# Sheet1.net
KiCad netlist of a schematic drawn in Altium Designer
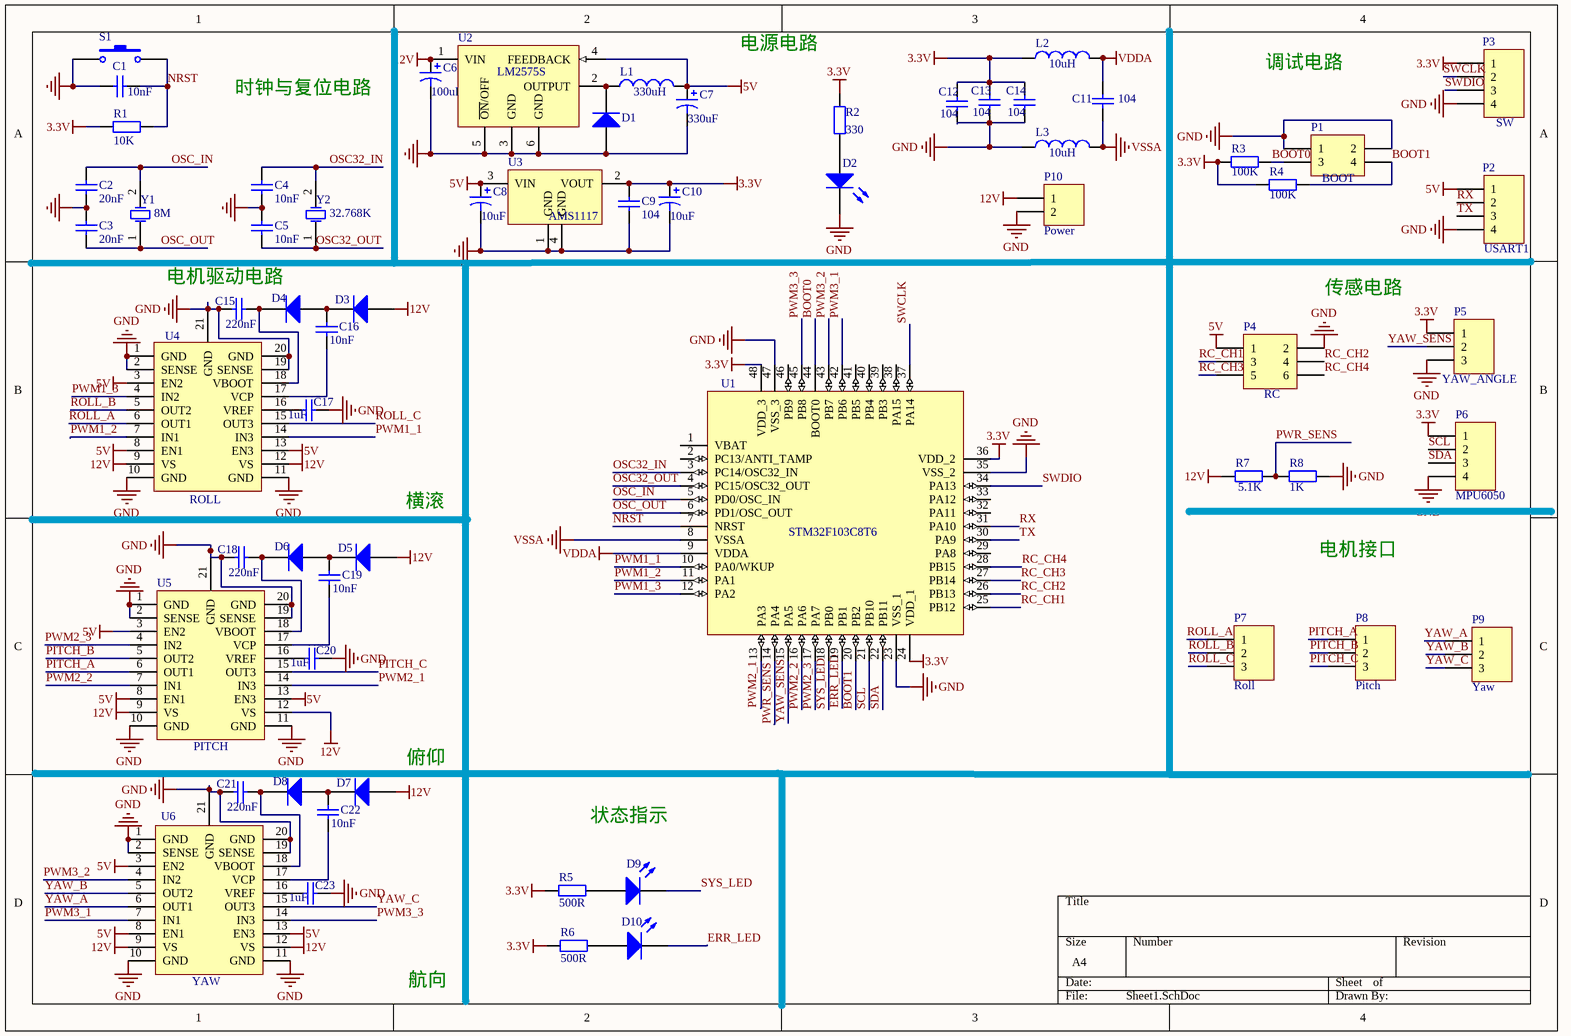
[diagram p0: Sheet1.SchDoc]

(export (version "E")
  (design (tool "Eeschema 10.0.6"))
  (components
    (comp (ref "C1")
      (value "10nF")
      (footprint "0603")
      (description "Capacitor")
      (fields (field (name "Comment") "Cap") (field (name "PUBLISHER") "Altium Limited"))
      (libsource (lib "Miscellaneous Devices") (part "Cap"))
    )
    (comp (ref "C2")
      (value "20nF")
      (footprint "0603")
      (description "Capacitor")
      (fields (field (name "Comment") "Cap") (field (name "PUBLISHER") "Altium Limited"))
      (libsource (lib "Miscellaneous Devices") (part "Cap"))
    )
    (comp (ref "C3")
      (value "20nF")
      (footprint "0603")
      (description "Capacitor")
      (fields (field (name "Comment") "Cap") (field (name "PUBLISHER") "Altium Limited"))
      (libsource (lib "Miscellaneous Devices") (part "Cap"))
    )
    (comp (ref "C4")
      (value "10nF")
      (footprint "0603")
      (description "Capacitor")
      (fields (field (name "Comment") "Cap") (field (name "PUBLISHER") "Altium Limited"))
      (libsource (lib "Miscellaneous Devices") (part "Cap"))
    )
    (comp (ref "C5")
      (value "10nF")
      (footprint "0603")
      (description "Capacitor")
      (fields (field (name "Comment") "Cap") (field (name "PUBLISHER") "Altium Limited"))
      (libsource (lib "Miscellaneous Devices") (part "Cap"))
    )
    (comp (ref "C6")
      (value "100uF")
      (footprint "25V 100uF 6*7")
      (description "Polarized Capacitor (Radial)")
      (fields (field (name "Comment") "Cap Pol1") (field (name "PUBLISHER") "Altium Limited"))
      (libsource (lib "Miscellaneous Devices") (part "Cap Pol1"))
    )
    (comp (ref "C7")
      (value "330uF")
      (footprint "25V 330uF 8*10")
      (description "Polarized Capacitor (Radial)")
      (fields (field (name "Comment") "Cap Pol1") (field (name "PUBLISHER") "Altium Limited"))
      (libsource (lib "Miscellaneous Devices") (part "Cap Pol1"))
    )
    (comp (ref "C8")
      (value "10uF")
      (footprint "1206")
      (description "Polarized Capacitor (Radial)")
      (fields (field (name "Comment") "Cap Pol1") (field (name "PUBLISHER") "Altium Limited"))
      (libsource (lib "Miscellaneous Devices") (part "Cap Pol1"))
    )
    (comp (ref "C9")
      (value "104")
      (footprint "0603")
      (description "Capacitor")
      (fields (field (name "Comment") "Cap") (field (name "PUBLISHER") "Altium Limited"))
      (libsource (lib "Miscellaneous Devices") (part "Cap"))
    )
    (comp (ref "C10")
      (value "10uF")
      (footprint "1206")
      (description "Polarized Capacitor (Radial)")
      (fields (field (name "Comment") "Cap Pol1") (field (name "PUBLISHER") "Altium Limited"))
      (libsource (lib "Miscellaneous Devices") (part "Cap Pol1"))
    )
    (comp (ref "C11")
      (value "104")
      (footprint "0603")
      (description "Capacitor")
      (fields (field (name "Comment") "Cap") (field (name "PUBLISHER") "Altium Limited"))
      (libsource (lib "Miscellaneous Devices") (part "Cap"))
    )
    (comp (ref "C12")
      (value "104")
      (footprint "0603")
      (description "Capacitor")
      (fields (field (name "Comment") "Cap") (field (name "PUBLISHER") "Altium Limited"))
      (libsource (lib "Miscellaneous Devices") (part "Cap"))
    )
    (comp (ref "C13")
      (value "104")
      (footprint "0603")
      (description "Capacitor")
      (fields (field (name "Comment") "Cap") (field (name "PUBLISHER") "Altium Limited"))
      (libsource (lib "Miscellaneous Devices") (part "Cap"))
    )
    (comp (ref "C14")
      (value "104")
      (footprint "0603")
      (description "Capacitor")
      (fields (field (name "Comment") "Cap") (field (name "PUBLISHER") "Altium Limited"))
      (libsource (lib "Miscellaneous Devices") (part "Cap"))
    )
    (comp (ref "C15")
      (value "220nF")
      (footprint "0603")
      (description "Capacitor")
      (fields (field (name "Comment") "Cap") (field (name "PUBLISHER") "Altium Limited"))
      (libsource (lib "Miscellaneous Devices") (part "Cap"))
    )
    (comp (ref "C16")
      (value "10nF")
      (footprint "0603")
      (description "Capacitor")
      (fields (field (name "Comment") "Cap") (field (name "PUBLISHER") "Altium Limited"))
      (libsource (lib "Miscellaneous Devices") (part "Cap"))
    )
    (comp (ref "C17")
      (value "1uF")
      (footprint "0603")
      (description "Capacitor")
      (fields (field (name "Comment") "Cap") (field (name "PUBLISHER") "Altium Limited"))
      (libsource (lib "Miscellaneous Devices") (part "Cap"))
    )
    (comp (ref "C18")
      (value "220nF")
      (footprint "0603")
      (description "Capacitor")
      (fields (field (name "Comment") "Cap") (field (name "PUBLISHER") "Altium Limited"))
      (libsource (lib "Miscellaneous Devices") (part "Cap"))
    )
    (comp (ref "C19")
      (value "10nF")
      (footprint "0603")
      (description "Capacitor")
      (fields (field (name "Comment") "Cap") (field (name "PUBLISHER") "Altium Limited"))
      (libsource (lib "Miscellaneous Devices") (part "Cap"))
    )
    (comp (ref "C20")
      (value "1uF")
      (footprint "0603")
      (description "Capacitor")
      (fields (field (name "Comment") "Cap") (field (name "PUBLISHER") "Altium Limited"))
      (libsource (lib "Miscellaneous Devices") (part "Cap"))
    )
    (comp (ref "C21")
      (value "220nF")
      (footprint "0603")
      (description "Capacitor")
      (fields (field (name "Comment") "Cap") (field (name "PUBLISHER") "Altium Limited"))
      (libsource (lib "Miscellaneous Devices") (part "Cap"))
    )
    (comp (ref "C22")
      (value "10nF")
      (footprint "0603")
      (description "Capacitor")
      (fields (field (name "Comment") "Cap") (field (name "PUBLISHER") "Altium Limited"))
      (libsource (lib "Miscellaneous Devices") (part "Cap"))
    )
    (comp (ref "C23")
      (value "1uF")
      (footprint "0603")
      (description "Capacitor")
      (fields (field (name "Comment") "Cap") (field (name "PUBLISHER") "Altium Limited"))
      (libsource (lib "Miscellaneous Devices") (part "Cap"))
    )
    (comp (ref "D1")
      (value "Diode 1N4003")
      (footprint "SMA")
      (description "1 Amp General Purpose Rectifier")
      (fields (field (name "PUBLISHER") "Altium Limited"))
      (libsource (lib "Miscellaneous Devices") (part "Diode 1N4003"))
    )
    (comp (ref "D2")
      (value "D2")
      (footprint "0805")
      (description "Typical BLUE SiC LED")
      (fields (field (name "PUBLISHER") "Altium Limited"))
      (libsource (lib "Miscellaneous Devices") (part "LED3"))
    )
    (comp (ref "D3")
      (value "Diode 1N914")
      (footprint "0805")
      (description "High Conductance Fast Diode")
      (fields (field (name "PUBLISHER") "Altium Limited"))
      (libsource (lib "Miscellaneous Devices") (part "Diode 1N914"))
    )
    (comp (ref "D4")
      (value "Diode 1N914")
      (footprint "0805")
      (description "High Conductance Fast Diode")
      (fields (field (name "PUBLISHER") "Altium Limited"))
      (libsource (lib "Miscellaneous Devices") (part "Diode 1N914"))
    )
    (comp (ref "D5")
      (value "Diode 1N914")
      (footprint "0805")
      (description "High Conductance Fast Diode")
      (fields (field (name "PUBLISHER") "Altium Limited"))
      (libsource (lib "Miscellaneous Devices") (part "Diode 1N914"))
    )
    (comp (ref "D6")
      (value "Diode 1N914")
      (footprint "0805")
      (description "High Conductance Fast Diode")
      (fields (field (name "PUBLISHER") "Altium Limited"))
      (libsource (lib "Miscellaneous Devices") (part "Diode 1N914"))
    )
    (comp (ref "D7")
      (value "Diode 1N914")
      (footprint "0805")
      (description "High Conductance Fast Diode")
      (fields (field (name "PUBLISHER") "Altium Limited"))
      (libsource (lib "Miscellaneous Devices") (part "Diode 1N914"))
    )
    (comp (ref "D8")
      (value "Diode 1N914")
      (footprint "0805")
      (description "High Conductance Fast Diode")
      (fields (field (name "PUBLISHER") "Altium Limited"))
      (libsource (lib "Miscellaneous Devices") (part "Diode 1N914"))
    )
    (comp (ref "D9")
      (value "D2")
      (footprint "0805")
      (description "Typical BLUE SiC LED")
      (fields (field (name "PUBLISHER") "Altium Limited"))
      (libsource (lib "Miscellaneous Devices") (part "LED3"))
    )
    (comp (ref "D10")
      (value "D2")
      (footprint "0805")
      (description "Typical BLUE SiC LED")
      (fields (field (name "PUBLISHER") "Altium Limited"))
      (libsource (lib "Miscellaneous Devices") (part "LED3"))
    )
    (comp (ref "L1")
      (value "330uH")
      (footprint "330uH 5.8*5*4")
      (description "Inductor")
      (fields (field (name "PUBLISHER") "Altium Limited"))
      (libsource (lib "Miscellaneous Devices") (part "Inductor"))
    )
    (comp (ref "L2")
      (value "10uH")
      (footprint "0603")
      (description "Inductor")
      (fields (field (name "PUBLISHER") "Altium Limited"))
      (libsource (lib "Miscellaneous Devices") (part "Inductor"))
    )
    (comp (ref "L3")
      (value "10uH")
      (footprint "0603")
      (description "Inductor")
      (fields (field (name "PUBLISHER") "Altium Limited"))
      (libsource (lib "Miscellaneous Devices") (part "Inductor"))
    )
    (comp (ref "P1")
      (value "BOOT")
      (footprint "2x2P 2mm")
      (description "Header, 2-Pin, Dual row")
      (fields (field (name "PUBLISHER") "Altium Limited"))
      (libsource (lib "Miscellaneous Connectors") (part "Header 2X2"))
    )
    (comp (ref "P2")
      (value "USART1")
      (footprint "4P 2mm")
      (description "Header, 4-Pin, Right Angle")
      (fields (field (name "PUBLISHER") "Altium Limited"))
      (libsource (lib "Miscellaneous Connectors") (part "Header 4H"))
    )
    (comp (ref "P3")
      (value "SW")
      (footprint "4P 2mm")
      (description "Header, 4-Pin, Right Angle")
      (fields (field (name "PUBLISHER") "Altium Limited"))
      (libsource (lib "Miscellaneous Connectors") (part "Header 4H"))
    )
    (comp (ref "P4")
      (value "RC")
      (footprint "6P 2mm")
      (description "Header, 3-Pin, Dual row")
      (fields (field (name "PUBLISHER") "Altium Limited"))
      (libsource (lib "Miscellaneous Connectors") (part "Header 3X2"))
    )
    (comp (ref "P5")
      (value "YAW_ANGLE")
      (footprint "3P 2mm")
      (description "Header, 3-Pin")
      (fields (field (name "PUBLISHER") "Altium Limited"))
      (libsource (lib "Miscellaneous Connectors") (part "Header 3"))
    )
    (comp (ref "P6")
      (value "MPU6050")
      (footprint "4P 2mm")
      (description "Header, 4-Pin")
      (fields (field (name "PUBLISHER") "Altium Limited"))
      (libsource (lib "Miscellaneous Connectors") (part "Header 4"))
    )
    (comp (ref "P7")
      (value "Roll")
      (footprint "3P 2mm")
      (description "Header, 3-Pin")
      (fields (field (name "PUBLISHER") "Altium Limited"))
      (libsource (lib "Miscellaneous Connectors") (part "Header 3"))
    )
    (comp (ref "P8")
      (value "Pitch")
      (footprint "3P 2mm")
      (description "Header, 3-Pin")
      (fields (field (name "PUBLISHER") "Altium Limited"))
      (libsource (lib "Miscellaneous Connectors") (part "Header 3"))
    )
    (comp (ref "P9")
      (value "Yaw")
      (footprint "3P 2mm")
      (description "Header, 3-Pin")
      (fields (field (name "PUBLISHER") "Altium Limited"))
      (libsource (lib "Miscellaneous Connectors") (part "Header 3"))
    )
    (comp (ref "P10")
      (value "Power")
      (footprint "2P 2mm")
      (description "Header, 2-Pin")
      (fields (field (name "PUBLISHER") "Altium Limited"))
      (libsource (lib "Miscellaneous Connectors") (part "Header 2"))
    )
    (comp (ref "R1")
      (value "10K")
      (footprint "0603")
      (description "Resistor")
      (fields (field (name "Comment") "Res2") (field (name "PUBLISHER") "Altium Limited"))
      (libsource (lib "Miscellaneous Devices") (part "Res2"))
    )
    (comp (ref "R2")
      (value "330")
      (footprint "0603")
      (description "Resistor")
      (fields (field (name "Comment") "Res2") (field (name "PUBLISHER") "Altium Limited"))
      (libsource (lib "") (part "Res2_1"))
    )
    (comp (ref "R3")
      (value "100K")
      (footprint "0603")
      (description "Resistor")
      (fields (field (name "Comment") "Res2") (field (name "PUBLISHER") "Altium Limited"))
      (libsource (lib "Miscellaneous Devices") (part "Res2"))
    )
    (comp (ref "R4")
      (value "100K")
      (footprint "0603")
      (description "Resistor")
      (fields (field (name "Comment") "Res2") (field (name "PUBLISHER") "Altium Limited"))
      (libsource (lib "Miscellaneous Devices") (part "Res2"))
    )
    (comp (ref "R5")
      (value "500R")
      (footprint "0603")
      (description "Resistor")
      (fields (field (name "Comment") "Res2") (field (name "PUBLISHER") "Altium Limited"))
      (libsource (lib "Miscellaneous Devices") (part "Res2"))
    )
    (comp (ref "R6")
      (value "500R")
      (footprint "0603")
      (description "Resistor")
      (fields (field (name "Comment") "Res2") (field (name "PUBLISHER") "Altium Limited"))
      (libsource (lib "Miscellaneous Devices") (part "Res2"))
    )
    (comp (ref "R7")
      (value "5.1K")
      (footprint "0603")
      (description "Resistor")
      (fields (field (name "Comment") "Res2") (field (name "PUBLISHER") "Altium Limited"))
      (libsource (lib "Miscellaneous Devices") (part "Res2"))
    )
    (comp (ref "R8")
      (value "1K")
      (footprint "0603")
      (description "Resistor")
      (fields (field (name "Comment") "Res2") (field (name "PUBLISHER") "Altium Limited"))
      (libsource (lib "Miscellaneous Devices") (part "Res2"))
    )
    (comp (ref "S1")
      (value "SW-PB")
      (footprint "SW3*6")
      (description "Switch")
      (fields (field (name "PUBLISHER") "Altium Limited"))
      (libsource (lib "Miscellaneous Devices") (part "SW-PB"))
    )
    (comp (ref "U1")
      (value "STM32F103C8T6")
      (footprint "STM32F103C8T6")
      (libsource (lib "Schlib1") (part "STM32F103C8T6"))
    )
    (comp (ref "U2")
      (value "LM2575S")
      (footprint "LM2575S-TO-263-5")
      (libsource (lib "Schlib1") (part "LM2575S"))
    )
    (comp (ref "U3") (value "AMS1117") (footprint "AMS1117") (libsource (lib "Schlib1") (part "AMS1117")))
    (comp (ref "U4") (value "L6234D") (footprint "L6234DD") (libsource (lib "Schlib1") (part "L6234D")))
    (comp (ref "U5") (value "L6234D") (footprint "L6234DD") (libsource (lib "Schlib1") (part "L6234D")))
    (comp (ref "U6") (value "L6234D") (footprint "L6234DD") (libsource (lib "Schlib1") (part "L6234D")))
    (comp (ref "Y1")
      (value "8M")
      (footprint "XTAL 8M")
      (description "Crystal Oscillator")
      (fields (field (name "PUBLISHER") "Altium Limited"))
      (libsource (lib "Miscellaneous Devices") (part "XTAL"))
    )
    (comp (ref "Y2")
      (value "32.768K")
      (footprint "XTAL 32.768K")
      (description "Crystal Oscillator")
      (fields (field (name "PUBLISHER") "Altium Limited"))
      (libsource (lib "Miscellaneous Devices") (part "XTAL"))
    )
  )
  (nets
    (net (code "1") (name "/BOOT0") (class "Default")
      (node (ref "P1") (pin "3") (pinfunction "3_3") (pintype "passive"))
      (node (ref "R3") (pin "2") (pinfunction "2_2") (pintype "passive"))
      (node (ref "U1") (pin "44") (pinfunction "BOOT0_44") (pintype "passive"))
    )
    (net (code "2") (name "/BOOT1") (class "Default")
      (node (ref "P1") (pin "4") (pinfunction "4_4") (pintype "passive"))
      (node (ref "R4") (pin "2") (pinfunction "2_2") (pintype "passive"))
      (node (ref "U1") (pin "20") (pinfunction "PB2_20") (pintype "bidirectional"))
    )
    (net (code "3") (name "/ERR_LED") (class "Default")
      (node (ref "D10") (pin "2") (pinfunction "K_2") (pintype "passive"))
      (node (ref "U1") (pin "19") (pinfunction "PB1_19") (pintype "bidirectional"))
    )
    (net (code "4") (name "/NRST") (class "Default")
      (node (ref "C1") (pin "2") (pinfunction "2_2") (pintype "passive"))
      (node (ref "R1") (pin "2") (pinfunction "2_2") (pintype "passive"))
      (node (ref "S1") (pin "2") (pinfunction "2_2") (pintype "passive"))
      (node (ref "U1") (pin "7") (pinfunction "NRST_7") (pintype "passive"))
    )
    (net (code "5") (name "/OSC32_IN") (class "Default")
      (node (ref "C4") (pin "2") (pinfunction "2_2") (pintype "passive"))
      (node (ref "U1") (pin "3") (pinfunction "PC14/OSC32_IN_3") (pintype "bidirectional"))
      (node (ref "Y2") (pin "2") (pinfunction "OSC2_2") (pintype "passive"))
    )
    (net (code "6") (name "/OSC32_OUT") (class "Default")
      (node (ref "C5") (pin "1") (pinfunction "1_1") (pintype "passive"))
      (node (ref "U1") (pin "4") (pinfunction "PC15/OSC32_OUT_4") (pintype "bidirectional"))
      (node (ref "Y2") (pin "1") (pinfunction "OSC1_1") (pintype "passive"))
    )
    (net (code "7") (name "/OSC_IN") (class "Default")
      (node (ref "C2") (pin "2") (pinfunction "2_2") (pintype "passive"))
      (node (ref "U1") (pin "5") (pinfunction "PD0/OSC_IN_5") (pintype "bidirectional"))
      (node (ref "Y1") (pin "2") (pinfunction "OSC2_2") (pintype "passive"))
    )
    (net (code "8") (name "/OSC_OUT") (class "Default")
      (node (ref "C3") (pin "1") (pinfunction "1_1") (pintype "passive"))
      (node (ref "U1") (pin "6") (pinfunction "PD1/OSC_OUT_6") (pintype "bidirectional"))
      (node (ref "Y1") (pin "1") (pinfunction "OSC1_1") (pintype "passive"))
    )
    (net (code "9") (name "/PITCH_A") (class "Default")
      (node (ref "P8") (pin "1") (pinfunction "1_1") (pintype "passive"))
      (node (ref "U5") (pin "6") (pinfunction "OUT1_6") (pintype "passive"))
    )
    (net (code "10") (name "/PITCH_B") (class "Default")
      (node (ref "P8") (pin "2") (pinfunction "2_2") (pintype "passive"))
      (node (ref "U5") (pin "5") (pinfunction "OUT2_5") (pintype "passive"))
    )
    (net (code "11") (name "/PITCH_C") (class "Default")
      (node (ref "P8") (pin "3") (pinfunction "3_3") (pintype "passive"))
      (node (ref "U5") (pin "15") (pinfunction "OUT3_15") (pintype "passive"))
    )
    (net (code "12") (name "/PWM1_1") (class "Default")
      (node (ref "U1") (pin "10") (pinfunction "PA0/WKUP_10") (pintype "bidirectional"))
      (node (ref "U4") (pin "14") (pinfunction "IN3_14") (pintype "passive"))
    )
    (net (code "13") (name "/PWM1_2") (class "Default")
      (node (ref "U1") (pin "11") (pinfunction "PA1_11") (pintype "bidirectional"))
      (node (ref "U4") (pin "7") (pinfunction "IN1_7") (pintype "passive"))
    )
    (net (code "14") (name "/PWM1_3") (class "Default")
      (node (ref "U1") (pin "12") (pinfunction "PA2_12") (pintype "bidirectional"))
      (node (ref "U4") (pin "4") (pinfunction "IN2_4") (pintype "passive"))
    )
    (net (code "15") (name "/PWM2_1") (class "Default")
      (node (ref "U1") (pin "13") (pinfunction "PA3_13") (pintype "bidirectional"))
      (node (ref "U5") (pin "14") (pinfunction "IN3_14") (pintype "passive"))
    )
    (net (code "16") (name "/PWM2_2") (class "Default")
      (node (ref "U1") (pin "16") (pinfunction "PA6_16") (pintype "bidirectional"))
      (node (ref "U5") (pin "7") (pinfunction "IN1_7") (pintype "passive"))
    )
    (net (code "17") (name "/PWM2_3") (class "Default")
      (node (ref "U1") (pin "17") (pinfunction "PA7_17") (pintype "bidirectional"))
      (node (ref "U5") (pin "4") (pinfunction "IN2_4") (pintype "passive"))
    )
    (net (code "18") (name "/PWM3_1") (class "Default")
      (node (ref "U1") (pin "42") (pinfunction "PB6_42") (pintype "bidirectional"))
      (node (ref "U6") (pin "7") (pinfunction "IN1_7") (pintype "passive"))
    )
    (net (code "19") (name "/PWM3_2") (class "Default")
      (node (ref "U1") (pin "43") (pinfunction "PB7_43") (pintype "bidirectional"))
      (node (ref "U6") (pin "4") (pinfunction "IN2_4") (pintype "passive"))
    )
    (net (code "20") (name "/PWM3_3") (class "Default")
      (node (ref "U1") (pin "45") (pinfunction "PB8_45") (pintype "bidirectional"))
      (node (ref "U6") (pin "14") (pinfunction "IN3_14") (pintype "passive"))
    )
    (net (code "21") (name "/PWR_SENS") (class "Default")
      (node (ref "R7") (pin "2") (pinfunction "2_2") (pintype "passive"))
      (node (ref "R8") (pin "1") (pinfunction "1_1") (pintype "passive"))
      (node (ref "U1") (pin "14") (pinfunction "PA4_14") (pintype "bidirectional"))
    )
    (net (code "22") (name "/RC_CH1") (class "Default")
      (node (ref "P4") (pin "3") (pinfunction "3_3") (pintype "passive"))
      (node (ref "U1") (pin "25") (pinfunction "PB12_25") (pintype "bidirectional"))
    )
    (net (code "23") (name "/RC_CH2") (class "Default")
      (node (ref "P4") (pin "4") (pinfunction "4_4") (pintype "passive"))
      (node (ref "U1") (pin "26") (pinfunction "PB13_26") (pintype "bidirectional"))
    )
    (net (code "24") (name "/RC_CH3") (class "Default")
      (node (ref "P4") (pin "5") (pinfunction "5_5") (pintype "passive"))
      (node (ref "U1") (pin "27") (pinfunction "PB14_27") (pintype "bidirectional"))
    )
    (net (code "25") (name "/RC_CH4") (class "Default")
      (node (ref "P4") (pin "6") (pinfunction "6_6") (pintype "passive"))
      (node (ref "U1") (pin "28") (pinfunction "PB15_28") (pintype "bidirectional"))
    )
    (net (code "26") (name "/ROLL_A") (class "Default")
      (node (ref "P7") (pin "1") (pinfunction "1_1") (pintype "passive"))
      (node (ref "U4") (pin "6") (pinfunction "OUT1_6") (pintype "passive"))
    )
    (net (code "27") (name "/ROLL_B") (class "Default")
      (node (ref "P7") (pin "2") (pinfunction "2_2") (pintype "passive"))
      (node (ref "U4") (pin "5") (pinfunction "OUT2_5") (pintype "passive"))
    )
    (net (code "28") (name "/ROLL_C") (class "Default")
      (node (ref "P7") (pin "3") (pinfunction "3_3") (pintype "passive"))
      (node (ref "U4") (pin "15") (pinfunction "OUT3_15") (pintype "passive"))
    )
    (net (code "29") (name "/RX") (class "Default")
      (node (ref "P2") (pin "2") (pinfunction "2_2") (pintype "passive"))
      (node (ref "U1") (pin "31") (pinfunction "PA10_31") (pintype "bidirectional"))
    )
    (net (code "30") (name "/SCL") (class "Default")
      (node (ref "P6") (pin "2") (pinfunction "2_2") (pintype "passive"))
      (node (ref "U1") (pin "21") (pinfunction "PB10_21") (pintype "bidirectional"))
    )
    (net (code "31") (name "/SDA") (class "Default")
      (node (ref "P6") (pin "3") (pinfunction "3_3") (pintype "passive"))
      (node (ref "U1") (pin "22") (pinfunction "PB11_22") (pintype "bidirectional"))
    )
    (net (code "32") (name "/SWCLK") (class "Default")
      (node (ref "P3") (pin "2") (pinfunction "2_2") (pintype "passive"))
      (node (ref "U1") (pin "37") (pinfunction "PA14_37") (pintype "bidirectional"))
    )
    (net (code "33") (name "/SWDIO") (class "Default")
      (node (ref "P3") (pin "3") (pinfunction "3_3") (pintype "passive"))
      (node (ref "U1") (pin "34") (pinfunction "PA13_34") (pintype "bidirectional"))
    )
    (net (code "34") (name "/SYS_LED") (class "Default")
      (node (ref "D9") (pin "2") (pinfunction "K_2") (pintype "passive"))
      (node (ref "U1") (pin "18") (pinfunction "PB0_18") (pintype "bidirectional"))
    )
    (net (code "35") (name "/TX") (class "Default")
      (node (ref "P2") (pin "3") (pinfunction "3_3") (pintype "passive"))
      (node (ref "U1") (pin "30") (pinfunction "PA9_30") (pintype "bidirectional"))
    )
    (net (code "36") (name "/YAW_A") (class "Default")
      (node (ref "P9") (pin "1") (pinfunction "1_1") (pintype "passive"))
      (node (ref "U6") (pin "6") (pinfunction "OUT1_6") (pintype "passive"))
    )
    (net (code "37") (name "/YAW_B") (class "Default")
      (node (ref "P9") (pin "2") (pinfunction "2_2") (pintype "passive"))
      (node (ref "U6") (pin "5") (pinfunction "OUT2_5") (pintype "passive"))
    )
    (net (code "38") (name "/YAW_C") (class "Default")
      (node (ref "P9") (pin "3") (pinfunction "3_3") (pintype "passive"))
      (node (ref "U6") (pin "15") (pinfunction "OUT3_15") (pintype "passive"))
    )
    (net (code "39") (name "/YAW_SENS") (class "Default")
      (node (ref "P5") (pin "2") (pinfunction "2_2") (pintype "passive"))
      (node (ref "U1") (pin "15") (pinfunction "PA5_15") (pintype "bidirectional"))
    )
    (net (code "40") (name "3.3V") (class "Default")
      (node (ref "C10") (pin "1") (pinfunction "1_1") (pintype "passive"))
      (node (ref "C12") (pin "2") (pinfunction "2_2") (pintype "passive"))
      (node (ref "C13") (pin "2") (pinfunction "2_2") (pintype "passive"))
      (node (ref "C14") (pin "2") (pinfunction "2_2") (pintype "passive"))
      (node (ref "C9") (pin "2") (pinfunction "2_2") (pintype "passive"))
      (node (ref "L2") (pin "1") (pinfunction "1_1") (pintype "passive"))
      (node (ref "P3") (pin "1") (pinfunction "1_1") (pintype "passive"))
      (node (ref "P5") (pin "1") (pinfunction "1_1") (pintype "passive"))
      (node (ref "P6") (pin "1") (pinfunction "1_1") (pintype "passive"))
      (node (ref "R1") (pin "1") (pinfunction "1_1") (pintype "passive"))
      (node (ref "R2") (pin "2") (pinfunction "2_2") (pintype "passive"))
      (node (ref "R3") (pin "1") (pinfunction "1_1") (pintype "passive"))
      (node (ref "R4") (pin "1") (pinfunction "1_1") (pintype "passive"))
      (node (ref "R5") (pin "1") (pinfunction "1_1") (pintype "passive"))
      (node (ref "R6") (pin "1") (pinfunction "1_1") (pintype "passive"))
      (node (ref "U1") (pin "24") (pinfunction "VDD_1_24") (pintype "power_in"))
      (node (ref "U1") (pin "36") (pinfunction "VDD_2_36") (pintype "power_in"))
      (node (ref "U1") (pin "48") (pinfunction "VDD_3_48") (pintype "power_in"))
      (node (ref "U3") (pin "2") (pinfunction "VOUT_2") (pintype "power_in"))
    )
    (net (code "41") (name "5V") (class "Default")
      (node (ref "C7") (pin "1") (pinfunction "1_1") (pintype "passive"))
      (node (ref "C8") (pin "1") (pinfunction "1_1") (pintype "passive"))
      (node (ref "L1") (pin "2") (pinfunction "2_2") (pintype "passive"))
      (node (ref "P2") (pin "1") (pinfunction "1_1") (pintype "passive"))
      (node (ref "P4") (pin "1") (pinfunction "1_1") (pintype "passive"))
      (node (ref "U2") (pin "4") (pinfunction "FEEDBACK_4") (pintype "input"))
      (node (ref "U3") (pin "3") (pinfunction "VIN_3") (pintype "power_in"))
      (node (ref "U4") (pin "13") (pinfunction "EN3_13") (pintype "passive"))
      (node (ref "U4") (pin "3") (pinfunction "EN2_3") (pintype "passive"))
      (node (ref "U4") (pin "8") (pinfunction "EN1_8") (pintype "passive"))
      (node (ref "U5") (pin "13") (pinfunction "EN3_13") (pintype "passive"))
      (node (ref "U5") (pin "3") (pinfunction "EN2_3") (pintype "passive"))
      (node (ref "U5") (pin "8") (pinfunction "EN1_8") (pintype "passive"))
      (node (ref "U6") (pin "13") (pinfunction "EN3_13") (pintype "passive"))
      (node (ref "U6") (pin "3") (pinfunction "EN2_3") (pintype "passive"))
      (node (ref "U6") (pin "8") (pinfunction "EN1_8") (pintype "passive"))
    )
    (net (code "42") (name "12V") (class "Default")
      (node (ref "C6") (pin "1") (pinfunction "1_1") (pintype "passive"))
      (node (ref "D3") (pin "1") (pinfunction "A_1") (pintype "passive"))
      (node (ref "D5") (pin "1") (pinfunction "A_1") (pintype "passive"))
      (node (ref "D7") (pin "1") (pinfunction "A_1") (pintype "passive"))
      (node (ref "P10") (pin "1") (pinfunction "1_1") (pintype "passive"))
      (node (ref "R7") (pin "1") (pinfunction "1_1") (pintype "passive"))
      (node (ref "U2") (pin "1") (pinfunction "VIN_1") (pintype "power_in"))
      (node (ref "U4") (pin "12") (pinfunction "VS_12") (pintype "power_in"))
      (node (ref "U4") (pin "9") (pinfunction "VS_9") (pintype "power_in"))
      (node (ref "U5") (pin "12") (pinfunction "VS_12") (pintype "power_in"))
      (node (ref "U5") (pin "9") (pinfunction "VS_9") (pintype "power_in"))
      (node (ref "U6") (pin "12") (pinfunction "VS_12") (pintype "power_in"))
      (node (ref "U6") (pin "9") (pinfunction "VS_9") (pintype "power_in"))
    )
    (net (code "43") (name "GND") (class "Default")
      (node (ref "C1") (pin "1") (pinfunction "1_1") (pintype "passive"))
      (node (ref "C10") (pin "2") (pinfunction "2_2") (pintype "passive"))
      (node (ref "C12") (pin "1") (pinfunction "1_1") (pintype "passive"))
      (node (ref "C13") (pin "1") (pinfunction "1_1") (pintype "passive"))
      (node (ref "C14") (pin "1") (pinfunction "1_1") (pintype "passive"))
      (node (ref "C15") (pin "1") (pinfunction "1_1") (pintype "passive"))
      (node (ref "C17") (pin "1") (pinfunction "1_1") (pintype "passive"))
      (node (ref "C18") (pin "1") (pinfunction "1_1") (pintype "passive"))
      (node (ref "C2") (pin "1") (pinfunction "1_1") (pintype "passive"))
      (node (ref "C20") (pin "1") (pinfunction "1_1") (pintype "passive"))
      (node (ref "C21") (pin "1") (pinfunction "1_1") (pintype "passive"))
      (node (ref "C23") (pin "1") (pinfunction "1_1") (pintype "passive"))
      (node (ref "C3") (pin "2") (pinfunction "2_2") (pintype "passive"))
      (node (ref "C4") (pin "1") (pinfunction "1_1") (pintype "passive"))
      (node (ref "C5") (pin "2") (pinfunction "2_2") (pintype "passive"))
      (node (ref "C6") (pin "2") (pinfunction "2_2") (pintype "passive"))
      (node (ref "C7") (pin "2") (pinfunction "2_2") (pintype "passive"))
      (node (ref "C8") (pin "2") (pinfunction "2_2") (pintype "passive"))
      (node (ref "C9") (pin "1") (pinfunction "1_1") (pintype "passive"))
      (node (ref "D1") (pin "1") (pinfunction "A_1") (pintype "passive"))
      (node (ref "D2") (pin "2") (pinfunction "K_2") (pintype "passive"))
      (node (ref "L3") (pin "1") (pinfunction "1_1") (pintype "passive"))
      (node (ref "P1") (pin "1") (pinfunction "1_1") (pintype "passive"))
      (node (ref "P1") (pin "2") (pinfunction "2_2") (pintype "passive"))
      (node (ref "P10") (pin "2") (pinfunction "2_2") (pintype "passive"))
      (node (ref "P2") (pin "4") (pinfunction "4_4") (pintype "passive"))
      (node (ref "P3") (pin "4") (pinfunction "4_4") (pintype "passive"))
      (node (ref "P4") (pin "2") (pinfunction "2_2") (pintype "passive"))
      (node (ref "P5") (pin "3") (pinfunction "3_3") (pintype "passive"))
      (node (ref "P6") (pin "4") (pinfunction "4_4") (pintype "passive"))
      (node (ref "R8") (pin "2") (pinfunction "2_2") (pintype "passive"))
      (node (ref "S1") (pin "1") (pinfunction "1_1") (pintype "passive"))
      (node (ref "U1") (pin "23") (pinfunction "VSS_1_23") (pintype "power_in"))
      (node (ref "U1") (pin "35") (pinfunction "VSS_2_35") (pintype "power_in"))
      (node (ref "U1") (pin "47") (pinfunction "VSS_3_47") (pintype "power_in"))
      (node (ref "U2") (pin "3") (pinfunction "GND_3") (pintype "power_in"))
      (node (ref "U2") (pin "5") (pinfunction "~{ON}/OFF_5") (pintype "passive"))
      (node (ref "U2") (pin "6") (pinfunction "GND_6") (pintype "passive"))
      (node (ref "U3") (pin "1") (pinfunction "GND_1") (pintype "power_in"))
      (node (ref "U3") (pin "4") (pinfunction "GND_4") (pintype "passive"))
      (node (ref "U4") (pin "1") (pinfunction "GND_1") (pintype "power_in"))
      (node (ref "U4") (pin "10") (pinfunction "GND_10") (pintype "power_in"))
      (node (ref "U4") (pin "11") (pinfunction "GND_11") (pintype "power_in"))
      (node (ref "U4") (pin "19") (pinfunction "SENSE_19") (pintype "passive"))
      (node (ref "U4") (pin "2") (pinfunction "SENSE_2") (pintype "passive"))
      (node (ref "U4") (pin "20") (pinfunction "GND_20") (pintype "power_in"))
      (node (ref "U4") (pin "21") (pinfunction "GND_21") (pintype "passive"))
      (node (ref "U5") (pin "1") (pinfunction "GND_1") (pintype "power_in"))
      (node (ref "U5") (pin "10") (pinfunction "GND_10") (pintype "power_in"))
      (node (ref "U5") (pin "11") (pinfunction "GND_11") (pintype "power_in"))
      (node (ref "U5") (pin "19") (pinfunction "SENSE_19") (pintype "passive"))
      (node (ref "U5") (pin "2") (pinfunction "SENSE_2") (pintype "passive"))
      (node (ref "U5") (pin "20") (pinfunction "GND_20") (pintype "power_in"))
      (node (ref "U5") (pin "21") (pinfunction "GND_21") (pintype "passive"))
      (node (ref "U6") (pin "1") (pinfunction "GND_1") (pintype "power_in"))
      (node (ref "U6") (pin "10") (pinfunction "GND_10") (pintype "power_in"))
      (node (ref "U6") (pin "11") (pinfunction "GND_11") (pintype "power_in"))
      (node (ref "U6") (pin "19") (pinfunction "SENSE_19") (pintype "passive"))
      (node (ref "U6") (pin "2") (pinfunction "SENSE_2") (pintype "passive"))
      (node (ref "U6") (pin "20") (pinfunction "GND_20") (pintype "power_in"))
      (node (ref "U6") (pin "21") (pinfunction "GND_21") (pintype "passive"))
    )
    (net (code "44") (name "Net-(D1-K)") (class "Default")
      (node (ref "D1") (pin "2") (pinfunction "K_2") (pintype "passive"))
      (node (ref "L1") (pin "1") (pinfunction "1_1") (pintype "passive"))
      (node (ref "U2") (pin "2") (pinfunction "OUTPUT_2") (pintype "power_in"))
    )
    (net (code "45") (name "Net-(D2-A)") (class "Default")
      (node (ref "D2") (pin "1") (pinfunction "A_1") (pintype "passive"))
      (node (ref "R2") (pin "1") (pinfunction "1_1") (pintype "passive"))
    )
    (net (code "46") (name "Net-(D3-K)") (class "Default")
      (node (ref "C16") (pin "1") (pinfunction "1_1") (pintype "passive"))
      (node (ref "D3") (pin "2") (pinfunction "K_2") (pintype "passive"))
      (node (ref "D4") (pin "1") (pinfunction "A_1") (pintype "passive"))
    )
    (net (code "47") (name "Net-(D4-K)") (class "Default")
      (node (ref "C15") (pin "2") (pinfunction "2_2") (pintype "passive"))
      (node (ref "D4") (pin "2") (pinfunction "K_2") (pintype "passive"))
      (node (ref "U4") (pin "18") (pinfunction "VBOOT_18") (pintype "passive"))
    )
    (net (code "48") (name "Net-(D5-K)") (class "Default")
      (node (ref "C19") (pin "1") (pinfunction "1_1") (pintype "passive"))
      (node (ref "D5") (pin "2") (pinfunction "K_2") (pintype "passive"))
      (node (ref "D6") (pin "1") (pinfunction "A_1") (pintype "passive"))
    )
    (net (code "49") (name "Net-(D6-K)") (class "Default")
      (node (ref "C18") (pin "2") (pinfunction "2_2") (pintype "passive"))
      (node (ref "D6") (pin "2") (pinfunction "K_2") (pintype "passive"))
      (node (ref "U5") (pin "18") (pinfunction "VBOOT_18") (pintype "passive"))
    )
    (net (code "50") (name "Net-(D7-K)") (class "Default")
      (node (ref "C22") (pin "1") (pinfunction "1_1") (pintype "passive"))
      (node (ref "D7") (pin "2") (pinfunction "K_2") (pintype "passive"))
      (node (ref "D8") (pin "1") (pinfunction "A_1") (pintype "passive"))
    )
    (net (code "51") (name "Net-(D8-K)") (class "Default")
      (node (ref "C21") (pin "2") (pinfunction "2_2") (pintype "passive"))
      (node (ref "D8") (pin "2") (pinfunction "K_2") (pintype "passive"))
      (node (ref "U6") (pin "18") (pinfunction "VBOOT_18") (pintype "passive"))
    )
    (net (code "52") (name "Net-(D9-A)") (class "Default")
      (node (ref "D9") (pin "1") (pinfunction "A_1") (pintype "passive"))
      (node (ref "R5") (pin "2") (pinfunction "2_2") (pintype "passive"))
    )
    (net (code "53") (name "Net-(D10-A)") (class "Default")
      (node (ref "D10") (pin "1") (pinfunction "A_1") (pintype "passive"))
      (node (ref "R6") (pin "2") (pinfunction "2_2") (pintype "passive"))
    )
    (net (code "54") (name "Net-(U4-VCP)") (class "Default")
      (node (ref "C16") (pin "2") (pinfunction "2_2") (pintype "passive"))
      (node (ref "U4") (pin "17") (pinfunction "VCP_17") (pintype "passive"))
    )
    (net (code "55") (name "Net-(U4-VREF)") (class "Default")
      (node (ref "C17") (pin "2") (pinfunction "2_2") (pintype "passive"))
      (node (ref "U4") (pin "16") (pinfunction "VREF_16") (pintype "passive"))
    )
    (net (code "56") (name "Net-(U5-VCP)") (class "Default")
      (node (ref "C19") (pin "2") (pinfunction "2_2") (pintype "passive"))
      (node (ref "U5") (pin "17") (pinfunction "VCP_17") (pintype "passive"))
    )
    (net (code "57") (name "Net-(U5-VREF)") (class "Default")
      (node (ref "C20") (pin "2") (pinfunction "2_2") (pintype "passive"))
      (node (ref "U5") (pin "16") (pinfunction "VREF_16") (pintype "passive"))
    )
    (net (code "58") (name "Net-(U6-VCP)") (class "Default")
      (node (ref "C22") (pin "2") (pinfunction "2_2") (pintype "passive"))
      (node (ref "U6") (pin "17") (pinfunction "VCP_17") (pintype "passive"))
    )
    (net (code "59") (name "Net-(U6-VREF)") (class "Default")
      (node (ref "C23") (pin "2") (pinfunction "2_2") (pintype "passive"))
      (node (ref "U6") (pin "16") (pinfunction "VREF_16") (pintype "passive"))
    )
    (net (code "60") (name "VDDA") (class "Default")
      (node (ref "C11") (pin "2") (pinfunction "2_2") (pintype "passive"))
      (node (ref "L2") (pin "2") (pinfunction "2_2") (pintype "passive"))
      (node (ref "U1") (pin "9") (pinfunction "VDDA_9") (pintype "power_in"))
    )
    (net (code "61") (name "VSSA") (class "Default")
      (node (ref "C11") (pin "1") (pinfunction "1_1") (pintype "passive"))
      (node (ref "L3") (pin "2") (pinfunction "2_2") (pintype "passive"))
      (node (ref "U1") (pin "8") (pinfunction "VSSA_8") (pintype "power_in"))
    )
    (net (code "62") (name "unconnected-(U1-PA8-Pad29)") (class "Default")
      (node (ref "U1") (pin "29") (pinfunction "PA8_29") (pintype "bidirectional"))
    )
    (net (code "63") (name "unconnected-(U1-PA11-Pad32)") (class "Default")
      (node (ref "U1") (pin "32") (pinfunction "PA11_32") (pintype "bidirectional"))
    )
    (net (code "64") (name "unconnected-(U1-PA12-Pad33)") (class "Default")
      (node (ref "U1") (pin "33") (pinfunction "PA12_33") (pintype "bidirectional"))
    )
    (net (code "65") (name "unconnected-(U1-PA15-Pad38)") (class "Default")
      (node (ref "U1") (pin "38") (pinfunction "PA15_38") (pintype "bidirectional"))
    )
    (net (code "66") (name "unconnected-(U1-PB3-Pad39)") (class "Default")
      (node (ref "U1") (pin "39") (pinfunction "PB3_39") (pintype "bidirectional"))
    )
    (net (code "67") (name "unconnected-(U1-PB4-Pad40)") (class "Default")
      (node (ref "U1") (pin "40") (pinfunction "PB4_40") (pintype "bidirectional"))
    )
    (net (code "68") (name "unconnected-(U1-PB5-Pad41)") (class "Default")
      (node (ref "U1") (pin "41") (pinfunction "PB5_41") (pintype "bidirectional"))
    )
    (net (code "69") (name "unconnected-(U1-PB9-Pad46)") (class "Default")
      (node (ref "U1") (pin "46") (pinfunction "PB9_46") (pintype "bidirectional"))
    )
    (net (code "70") (name "unconnected-(U1-PC13{slash}ANTI_TAMP-Pad2)") (class "Default")
      (node (ref "U1") (pin "2") (pinfunction "PC13/ANTI_TAMP_2") (pintype "bidirectional"))
    )
    (net (code "71") (name "unconnected-(U1-VBAT-Pad1)") (class "Default")
      (node (ref "U1") (pin "1") (pinfunction "VBAT_1") (pintype "power_in"))
    )
  )
)
